# board.net
KiCad netlist of a schematic drawn in EAGLE
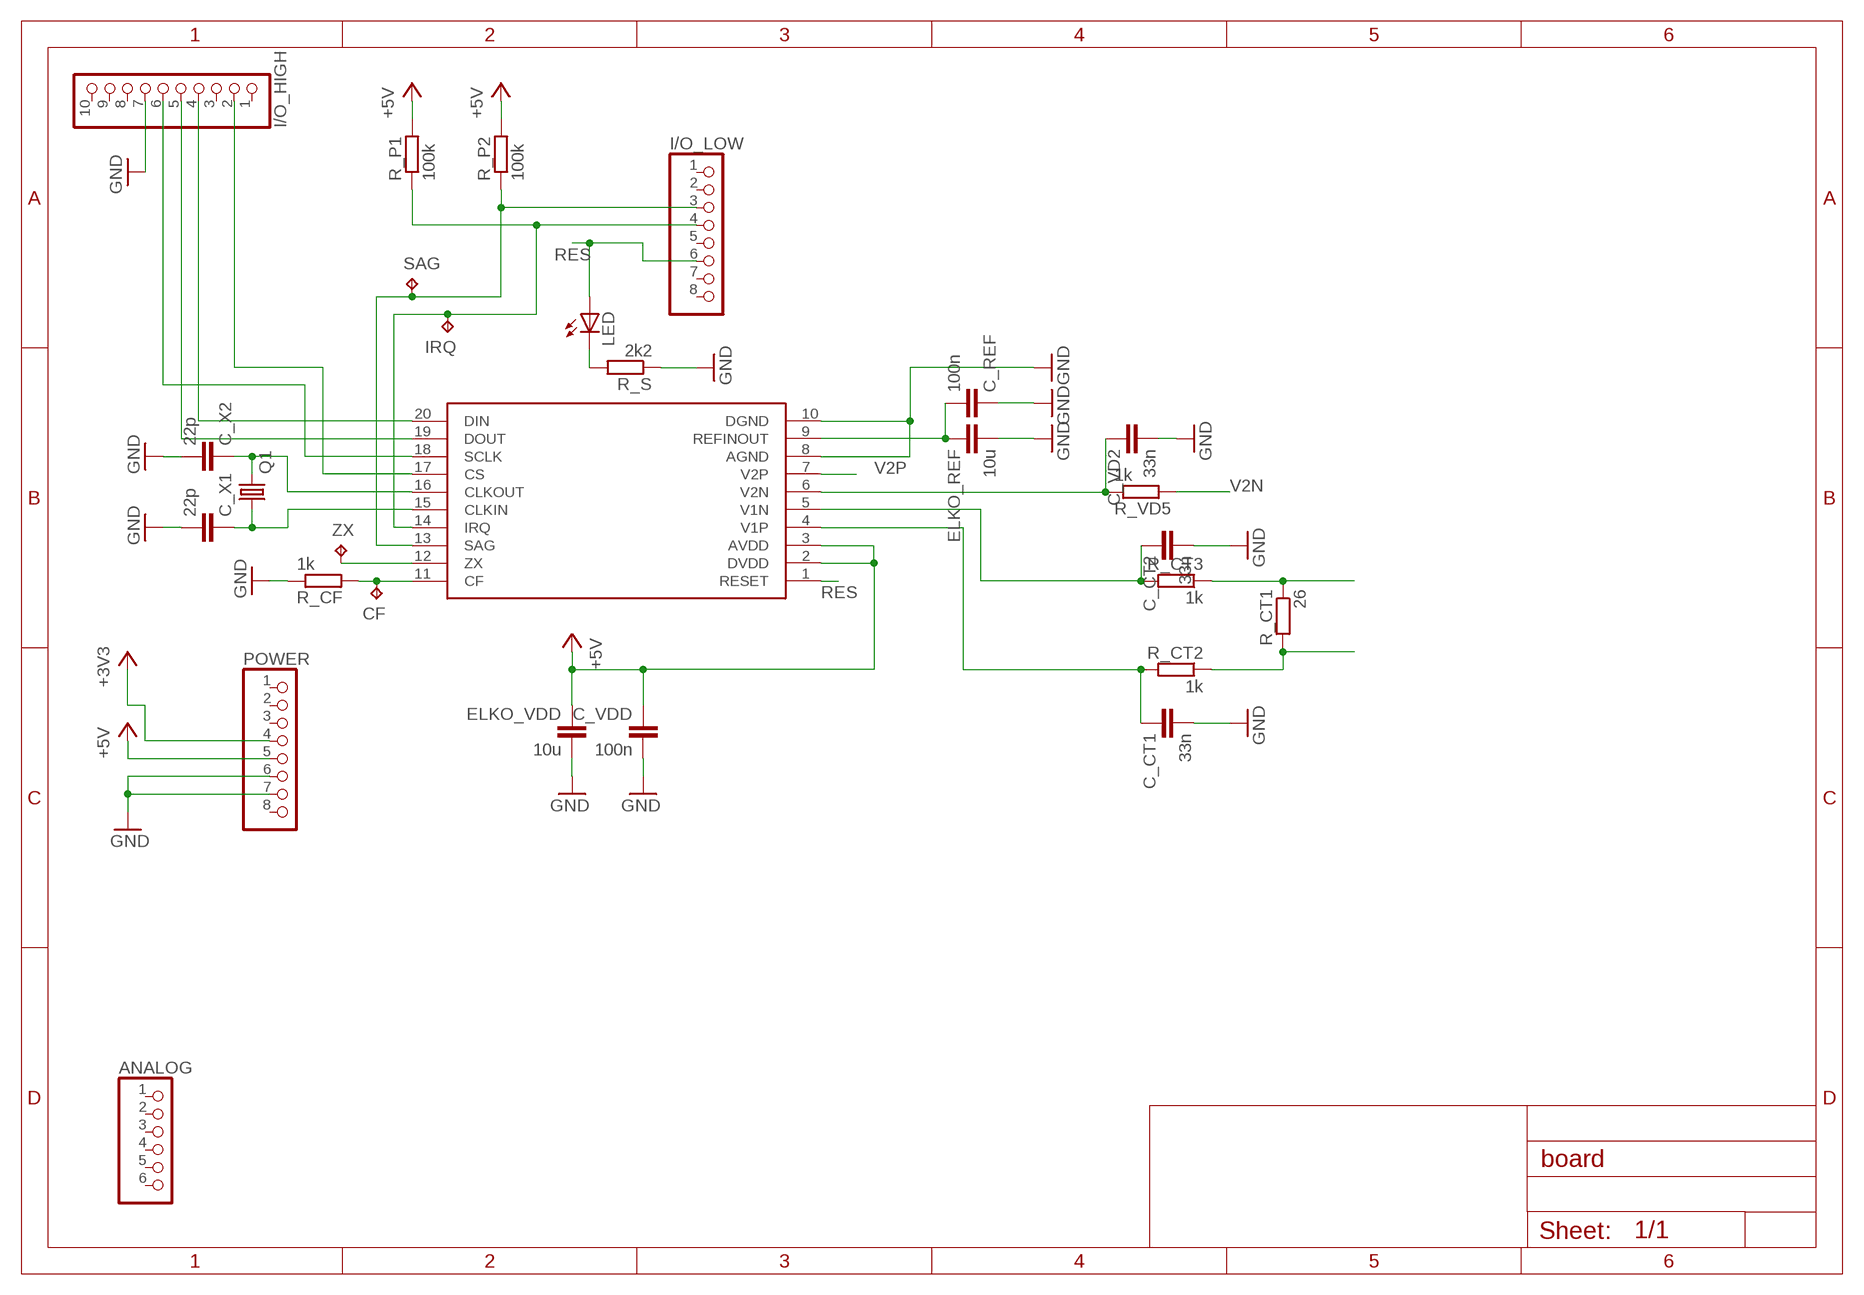
[diagram p0: schematic, sheet 1]

(export (version "E")
  (design (tool "Eeschema 10.0.6"))
  (components
    (comp (ref "ANALOG")
      (value "PINHD-1X6")
      (footprint "eagle-import:1X06")
      (libsource (lib "eagle-import") (part "PINHD-1X6"))
    )
    (comp (ref "CF")
      (value "TPPAD1-17")
      (footprint "eagle-import:P1-17")
      (libsource (lib "eagle-import") (part "TPPAD1-17"))
    )
    (comp (ref "C_CT1")
      (value "33n")
      (footprint "eagle-import:C1206K")
      (libsource (lib "eagle-import") (part "C-EUC1206K"))
    )
    (comp (ref "C_CT2")
      (value "33n")
      (footprint "eagle-import:C1206K")
      (libsource (lib "eagle-import") (part "C-EUC1206K"))
    )
    (comp (ref "C_REF")
      (value "100n")
      (footprint "eagle-import:C1206K")
      (libsource (lib "eagle-import") (part "C-EUC1206K"))
    )
    (comp (ref "C_VD2")
      (value "33n")
      (footprint "eagle-import:C1206K")
      (libsource (lib "eagle-import") (part "C-EUC1206K"))
    )
    (comp (ref "C_VDD")
      (value "100n")
      (footprint "eagle-import:C1206K")
      (libsource (lib "eagle-import") (part "C-EUC1206K"))
    )
    (comp (ref "C_X1")
      (value "22p")
      (footprint "eagle-import:C1206K")
      (libsource (lib "eagle-import") (part "C-EUC1206K"))
    )
    (comp (ref "C_X2")
      (value "22p")
      (footprint "eagle-import:C1206K")
      (libsource (lib "eagle-import") (part "C-EUC1206K"))
    )
    (comp (ref "ELKO_REF")
      (value "10u")
      (footprint "eagle-import:C7.5B3")
      (libsource (lib "eagle-import") (part "C7.5/3"))
    )
    (comp (ref "ELKO_VDD")
      (value "10u")
      (footprint "eagle-import:C7.5B3")
      (libsource (lib "eagle-import") (part "C7.5/3"))
    )
    (comp (ref "I/O_HIGH")
      (value "PINHD-1X10TH")
      (footprint "eagle-import:1X10-TH")
      (libsource (lib "eagle-import") (part "PINHD-1X10TH"))
    )
    (comp (ref "I/O_LOW")
      (value "PINHD-1X8TH")
      (footprint "eagle-import:1X08-TH")
      (libsource (lib "eagle-import") (part "PINHD-1X8TH"))
    )
    (comp (ref "IRQ")
      (value "TPPAD1-17")
      (footprint "eagle-import:P1-17")
      (libsource (lib "eagle-import") (part "TPPAD1-17"))
    )
    (comp (ref "LED")
      (value "LED3MM")
      (footprint "eagle-import:LED3MM")
      (libsource (lib "eagle-import") (part "LED3MM"))
    )
    (comp (ref "POWER")
      (value "PINHD-1X8TH")
      (footprint "eagle-import:1X08-TH")
      (libsource (lib "eagle-import") (part "PINHD-1X8TH"))
    )
    (comp (ref "Q1")
      (value "CRYSTALHC18U-V")
      (footprint "eagle-import:HC18U-V")
      (libsource (lib "eagle-import") (part "CRYSTALHC18U-V"))
    )
    (comp (ref "R_CF")
      (value "1k")
      (footprint "eagle-import:R2010")
      (libsource (lib "eagle-import") (part "R-EU_R2010"))
    )
    (comp (ref "R_CT1")
      (value "26")
      (footprint "eagle-import:R2512")
      (libsource (lib "eagle-import") (part "R-EU_R2512"))
    )
    (comp (ref "R_CT2")
      (value "1k")
      (footprint "eagle-import:R2010")
      (libsource (lib "eagle-import") (part "R-EU_R2010"))
    )
    (comp (ref "R_CT3")
      (value "1k")
      (footprint "eagle-import:R2010")
      (libsource (lib "eagle-import") (part "R-EU_R2010"))
    )
    (comp (ref "R_P1")
      (value "100k")
      (footprint "eagle-import:R2010")
      (libsource (lib "eagle-import") (part "R-EU_R2010"))
    )
    (comp (ref "R_P2")
      (value "100k")
      (footprint "eagle-import:R2010")
      (libsource (lib "eagle-import") (part "R-EU_R2010"))
    )
    (comp (ref "R_S")
      (value "2k2")
      (footprint "eagle-import:R2512")
      (libsource (lib "eagle-import") (part "R-EU_R2512"))
    )
    (comp (ref "R_VD5")
      (value "1k")
      (footprint "eagle-import:R2010")
      (libsource (lib "eagle-import") (part "R-EU_R2010"))
    )
    (comp (ref "SAG")
      (value "TPPAD1-17")
      (footprint "eagle-import:P1-17")
      (libsource (lib "eagle-import") (part "TPPAD1-17"))
    )
    (comp (ref "U$1")
      (value "ADE7753")
      (footprint "eagle-import:SSOP20")
      (libsource (lib "eagle-import") (part "ADE7753"))
    )
    (comp (ref "ZX")
      (value "TPPAD1-17")
      (footprint "eagle-import:P1-17")
      (libsource (lib "eagle-import") (part "TPPAD1-17"))
    )
  )
  (nets
    (net (code "1") (name "+3V3") (class "Default")
      (node (ref "POWER") (pin "4") (pinfunction "4_4") (pintype "passive"))
    )
    (net (code "2") (name "+5V") (class "Default")
      (node (ref "C_VDD") (pin "1") (pinfunction "1_1") (pintype "passive"))
      (node (ref "ELKO_VDD") (pin "1") (pinfunction "1_1") (pintype "passive"))
      (node (ref "POWER") (pin "5") (pinfunction "5_5") (pintype "passive"))
      (node (ref "R_P1") (pin "2") (pinfunction "2_2") (pintype "passive"))
      (node (ref "R_P2") (pin "2") (pinfunction "2_2") (pintype "passive"))
      (node (ref "U$1") (pin "2") (pinfunction "DVDD_2") (pintype "bidirectional"))
      (node (ref "U$1") (pin "3") (pinfunction "AVDD_3") (pintype "bidirectional"))
    )
    (net (code "3") (name "/RES") (class "Default")
      (node (ref "I/O_LOW") (pin "6") (pinfunction "6_6") (pintype "passive"))
      (node (ref "LED") (pin "A") (pinfunction "A_A") (pintype "passive"))
      (node (ref "U$1") (pin "1") (pinfunction "RESET_1") (pintype "bidirectional"))
    )
    (net (code "4") (name "/V2N") (class "Default")
      (node (ref "R_VD5") (pin "2") (pinfunction "2_2") (pintype "passive"))
    )
    (net (code "5") (name "/V2P") (class "Default")
      (node (ref "U$1") (pin "7") (pinfunction "V2P_7") (pintype "bidirectional"))
    )
    (net (code "6") (name "GND") (class "Default")
      (node (ref "C_CT1") (pin "2") (pinfunction "2_2") (pintype "passive"))
      (node (ref "C_CT2") (pin "2") (pinfunction "2_2") (pintype "passive"))
      (node (ref "C_REF") (pin "1") (pinfunction "1_1") (pintype "passive"))
      (node (ref "C_VD2") (pin "2") (pinfunction "2_2") (pintype "passive"))
      (node (ref "C_VDD") (pin "2") (pinfunction "2_2") (pintype "passive"))
      (node (ref "C_X1") (pin "2") (pinfunction "2_2") (pintype "passive"))
      (node (ref "C_X2") (pin "2") (pinfunction "2_2") (pintype "passive"))
      (node (ref "ELKO_REF") (pin "2") (pinfunction "2_2") (pintype "passive"))
      (node (ref "ELKO_VDD") (pin "2") (pinfunction "2_2") (pintype "passive"))
      (node (ref "I/O_HIGH") (pin "7") (pinfunction "7_7") (pintype "passive"))
      (node (ref "POWER") (pin "6") (pinfunction "6_6") (pintype "passive"))
      (node (ref "POWER") (pin "7") (pinfunction "7_7") (pintype "passive"))
      (node (ref "R_CF") (pin "1") (pinfunction "1_1") (pintype "passive"))
      (node (ref "R_S") (pin "1") (pinfunction "1_1") (pintype "passive"))
      (node (ref "U$1") (pin "10") (pinfunction "DGND_10") (pintype "bidirectional"))
      (node (ref "U$1") (pin "8") (pinfunction "AGND_8") (pintype "bidirectional"))
    )
    (net (code "7") (name "Net-(LED-C)") (class "Default")
      (node (ref "LED") (pin "K") (pinfunction "C_K") (pintype "passive"))
      (node (ref "R_S") (pin "2") (pinfunction "2_2") (pintype "passive"))
    )
    (net (code "8") (name "Net-(R_CT1-Pad1)") (class "Default")
      (node (ref "R_CT1") (pin "1") (pinfunction "1_1") (pintype "passive"))
      (node (ref "R_CT3") (pin "1") (pinfunction "1_1") (pintype "passive"))
    )
    (net (code "9") (name "Net-(R_CT1-Pad2)") (class "Default")
      (node (ref "R_CT1") (pin "2") (pinfunction "2_2") (pintype "passive"))
      (node (ref "R_CT2") (pin "1") (pinfunction "1_1") (pintype "passive"))
    )
    (net (code "10") (name "Net-(U$1-CF)") (class "Default")
      (node (ref "CF") (pin "TP") (pinfunction "TP_TP") (pintype "input"))
      (node (ref "R_CF") (pin "2") (pinfunction "2_2") (pintype "passive"))
      (node (ref "U$1") (pin "11") (pinfunction "CF_11") (pintype "bidirectional"))
    )
    (net (code "11") (name "Net-(U$1-CLKIN)") (class "Default")
      (node (ref "C_X1") (pin "1") (pinfunction "1_1") (pintype "passive"))
      (node (ref "Q1") (pin "1") (pinfunction "1_1") (pintype "passive"))
      (node (ref "U$1") (pin "15") (pinfunction "CLKIN_15") (pintype "bidirectional"))
    )
    (net (code "12") (name "Net-(U$1-CLKOUT)") (class "Default")
      (node (ref "C_X2") (pin "1") (pinfunction "1_1") (pintype "passive"))
      (node (ref "Q1") (pin "2") (pinfunction "2_2") (pintype "passive"))
      (node (ref "U$1") (pin "16") (pinfunction "CLKOUT_16") (pintype "bidirectional"))
    )
    (net (code "13") (name "Net-(U$1-CS)") (class "Default")
      (node (ref "I/O_HIGH") (pin "2") (pinfunction "2_2") (pintype "passive"))
      (node (ref "U$1") (pin "17") (pinfunction "CS_17") (pintype "bidirectional"))
    )
    (net (code "14") (name "Net-(U$1-DIN)") (class "Default")
      (node (ref "I/O_HIGH") (pin "4") (pinfunction "4_4") (pintype "passive"))
      (node (ref "U$1") (pin "20") (pinfunction "DIN_20") (pintype "bidirectional"))
    )
    (net (code "15") (name "Net-(U$1-DOUT)") (class "Default")
      (node (ref "I/O_HIGH") (pin "5") (pinfunction "5_5") (pintype "passive"))
      (node (ref "U$1") (pin "19") (pinfunction "DOUT_19") (pintype "bidirectional"))
    )
    (net (code "16") (name "Net-(U$1-IRQ)") (class "Default")
      (node (ref "I/O_LOW") (pin "4") (pinfunction "4_4") (pintype "passive"))
      (node (ref "IRQ") (pin "TP") (pinfunction "TP_TP") (pintype "input"))
      (node (ref "R_P1") (pin "1") (pinfunction "1_1") (pintype "passive"))
      (node (ref "U$1") (pin "14") (pinfunction "IRQ_14") (pintype "bidirectional"))
    )
    (net (code "17") (name "Net-(U$1-REFINOUT)") (class "Default")
      (node (ref "C_REF") (pin "2") (pinfunction "2_2") (pintype "passive"))
      (node (ref "ELKO_REF") (pin "1") (pinfunction "1_1") (pintype "passive"))
      (node (ref "U$1") (pin "9") (pinfunction "REFINOUT_9") (pintype "bidirectional"))
    )
    (net (code "18") (name "Net-(U$1-SAG)") (class "Default")
      (node (ref "I/O_LOW") (pin "3") (pinfunction "3_3") (pintype "passive"))
      (node (ref "R_P2") (pin "1") (pinfunction "1_1") (pintype "passive"))
      (node (ref "SAG") (pin "TP") (pinfunction "TP_TP") (pintype "input"))
      (node (ref "U$1") (pin "13") (pinfunction "SAG_13") (pintype "bidirectional"))
    )
    (net (code "19") (name "Net-(U$1-SCLK)") (class "Default")
      (node (ref "I/O_HIGH") (pin "6") (pinfunction "6_6") (pintype "passive"))
      (node (ref "U$1") (pin "18") (pinfunction "SCLK_18") (pintype "bidirectional"))
    )
    (net (code "20") (name "Net-(U$1-V1N)") (class "Default")
      (node (ref "C_CT2") (pin "1") (pinfunction "1_1") (pintype "passive"))
      (node (ref "R_CT3") (pin "2") (pinfunction "2_2") (pintype "passive"))
      (node (ref "U$1") (pin "5") (pinfunction "V1N_5") (pintype "bidirectional"))
    )
    (net (code "21") (name "Net-(U$1-V1P)") (class "Default")
      (node (ref "C_CT1") (pin "1") (pinfunction "1_1") (pintype "passive"))
      (node (ref "R_CT2") (pin "2") (pinfunction "2_2") (pintype "passive"))
      (node (ref "U$1") (pin "4") (pinfunction "V1P_4") (pintype "bidirectional"))
    )
    (net (code "22") (name "Net-(U$1-V2N)") (class "Default")
      (node (ref "C_VD2") (pin "1") (pinfunction "1_1") (pintype "passive"))
      (node (ref "R_VD5") (pin "1") (pinfunction "1_1") (pintype "passive"))
      (node (ref "U$1") (pin "6") (pinfunction "V2N_6") (pintype "bidirectional"))
    )
    (net (code "23") (name "Net-(U$1-ZX)") (class "Default")
      (node (ref "U$1") (pin "12") (pinfunction "ZX_12") (pintype "bidirectional"))
      (node (ref "ZX") (pin "TP") (pinfunction "TP_TP") (pintype "input"))
    )
    (net (code "24") (name "unconnected-(ANALOG-Pad1)") (class "Default")
      (node (ref "ANALOG") (pin "1") (pinfunction "1_1") (pintype "passive"))
    )
    (net (code "25") (name "unconnected-(ANALOG-Pad2)") (class "Default")
      (node (ref "ANALOG") (pin "2") (pinfunction "2_2") (pintype "passive"))
    )
    (net (code "26") (name "unconnected-(ANALOG-Pad3)") (class "Default")
      (node (ref "ANALOG") (pin "3") (pinfunction "3_3") (pintype "passive"))
    )
    (net (code "27") (name "unconnected-(ANALOG-Pad4)") (class "Default")
      (node (ref "ANALOG") (pin "4") (pinfunction "4_4") (pintype "passive"))
    )
    (net (code "28") (name "unconnected-(ANALOG-Pad5)") (class "Default")
      (node (ref "ANALOG") (pin "5") (pinfunction "5_5") (pintype "passive"))
    )
    (net (code "29") (name "unconnected-(ANALOG-Pad6)") (class "Default")
      (node (ref "ANALOG") (pin "6") (pinfunction "6_6") (pintype "passive"))
    )
    (net (code "30") (name "unconnected-(I/O_HIGH-Pad1)") (class "Default")
      (node (ref "I/O_HIGH") (pin "1") (pinfunction "1_1") (pintype "passive"))
    )
    (net (code "31") (name "unconnected-(I/O_HIGH-Pad3)") (class "Default")
      (node (ref "I/O_HIGH") (pin "3") (pinfunction "3_3") (pintype "passive"))
    )
    (net (code "32") (name "unconnected-(I/O_HIGH-Pad8)") (class "Default")
      (node (ref "I/O_HIGH") (pin "8") (pinfunction "8_8") (pintype "passive"))
    )
    (net (code "33") (name "unconnected-(I/O_HIGH-Pad9)") (class "Default")
      (node (ref "I/O_HIGH") (pin "9") (pinfunction "9_9") (pintype "passive"))
    )
    (net (code "34") (name "unconnected-(I/O_HIGH-Pad10)") (class "Default")
      (node (ref "I/O_HIGH") (pin "10") (pinfunction "10_10") (pintype "passive"))
    )
    (net (code "35") (name "unconnected-(I/O_LOW-Pad1)") (class "Default")
      (node (ref "I/O_LOW") (pin "1") (pinfunction "1_1") (pintype "passive"))
    )
    (net (code "36") (name "unconnected-(I/O_LOW-Pad2)") (class "Default")
      (node (ref "I/O_LOW") (pin "2") (pinfunction "2_2") (pintype "passive"))
    )
    (net (code "37") (name "unconnected-(I/O_LOW-Pad5)") (class "Default")
      (node (ref "I/O_LOW") (pin "5") (pinfunction "5_5") (pintype "passive"))
    )
    (net (code "38") (name "unconnected-(I/O_LOW-Pad7)") (class "Default")
      (node (ref "I/O_LOW") (pin "7") (pinfunction "7_7") (pintype "passive"))
    )
    (net (code "39") (name "unconnected-(I/O_LOW-Pad8)") (class "Default")
      (node (ref "I/O_LOW") (pin "8") (pinfunction "8_8") (pintype "passive"))
    )
    (net (code "40") (name "unconnected-(POWER-Pad1)") (class "Default")
      (node (ref "POWER") (pin "1") (pinfunction "1_1") (pintype "passive"))
    )
    (net (code "41") (name "unconnected-(POWER-Pad2)") (class "Default")
      (node (ref "POWER") (pin "2") (pinfunction "2_2") (pintype "passive"))
    )
    (net (code "42") (name "unconnected-(POWER-Pad3)") (class "Default")
      (node (ref "POWER") (pin "3") (pinfunction "3_3") (pintype "passive"))
    )
    (net (code "43") (name "unconnected-(POWER-Pad8)") (class "Default")
      (node (ref "POWER") (pin "8") (pinfunction "8_8") (pintype "passive"))
    )
  )
)
